# RK3566_FLASH_SD.net
KiCad netlist of a schematic drawn in Altium Designer
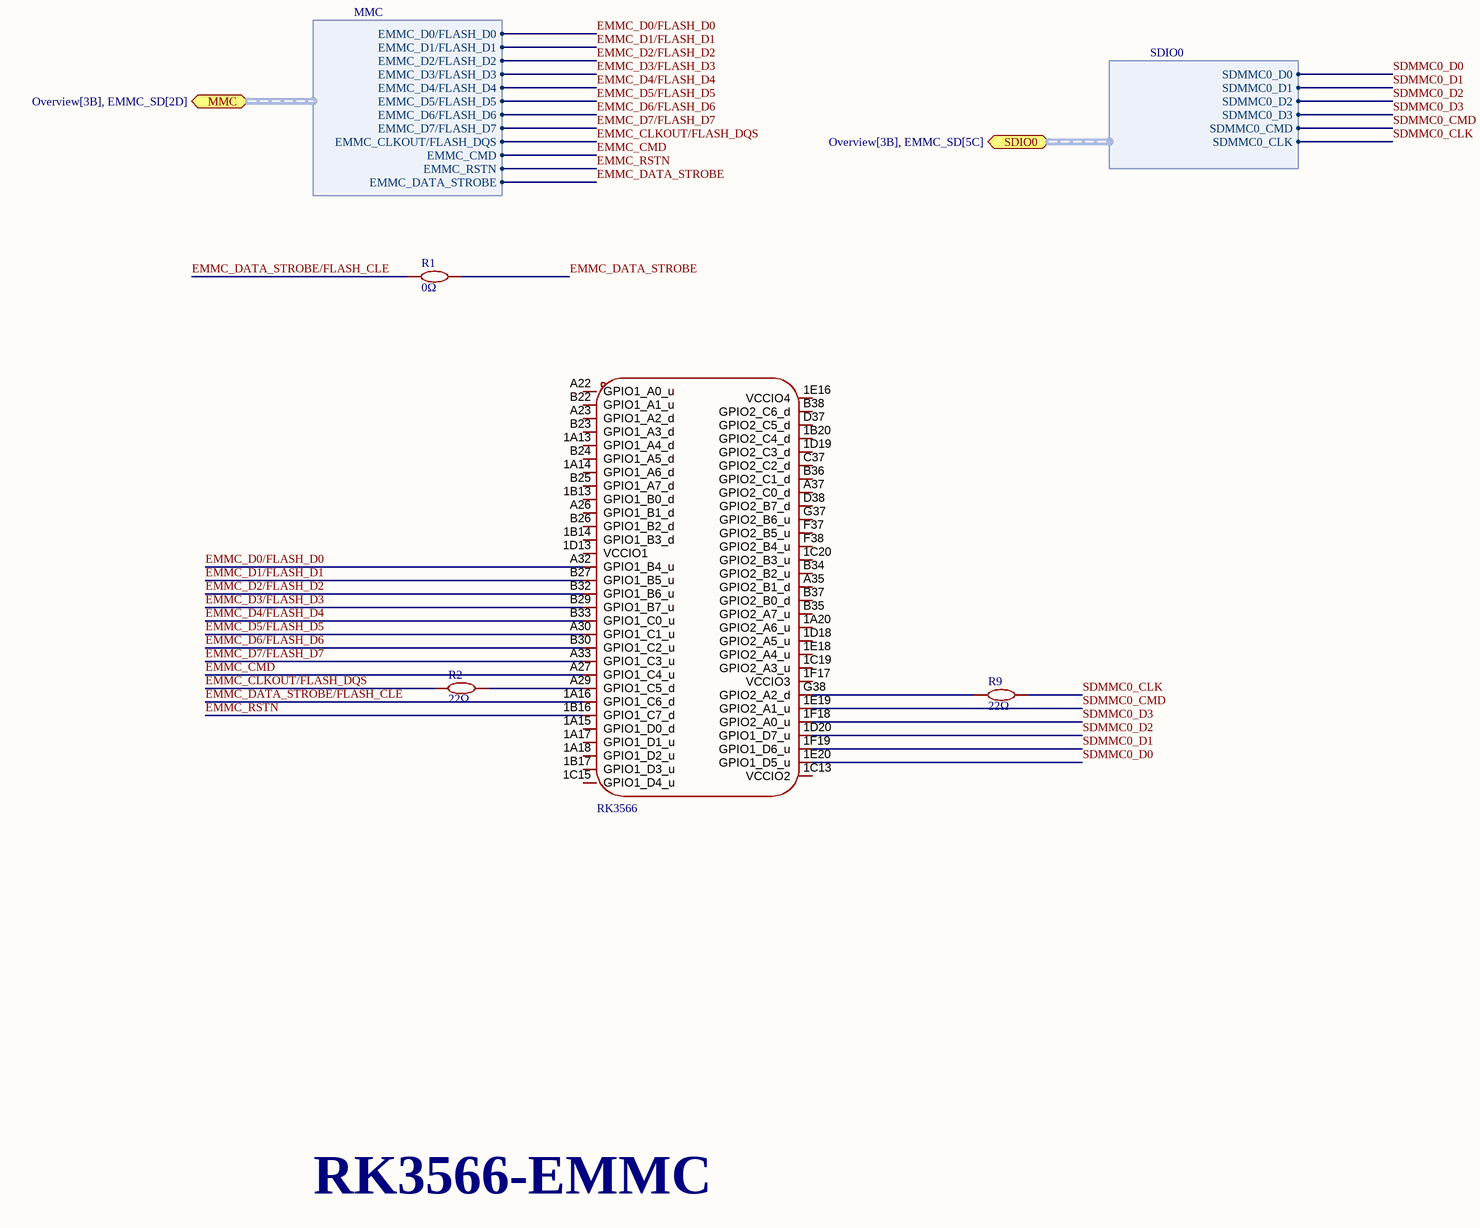
[diagram p0: RK3566_FLASH_SD.SchDoc]

(export (version "E")
  (design (tool "Eeschema 10.0.6"))
  (components
    (comp (ref "R1")
      (value "0Ω")
      (footprint "R0402")
      (description "0Ω 62.5mW 50V Thick Film Resistor ±1% 0402 Chip Resistor - Surface Mount ROHS")
      (libsource (lib "RLC") (part "0Ω"))
    )
    (comp (ref "R2")
      (value "22Ω")
      (footprint "R0402")
      (description "62.5mW 33Ω 50V ±100ppm/℃ Thick Film Resistor ±1% 0402 Chip Resistor - Surface Mount ROHS")
      (libsource (lib "RLC") (part "22Ω"))
    )
    (comp (ref "R9")
      (value "22Ω")
      (footprint "R0402")
      (description "62.5mW 33Ω 50V ±100ppm/℃ Thick Film Resistor ±1% 0402 Chip Resistor - Surface Mount ROHS")
      (libsource (lib "RLC") (part "22Ω"))
    )
    (comp (ref "U1")
      (value "RK3566")
      (footprint "BGA-565_L15.5-W14.4-P0.40_RK3566_1")
      (description "BGA-565(15.5x14.4)")
      (libsource (lib "IC") (part "RK3566"))
    )
  )
  (nets
    (net (code "3") (name "/EMMC_CLKOUT{slash}FLASH_DQS") (class "Default")
      (node (ref "R2") (pin "1") (pinfunction "1_1") (pintype "passive"))
    )
    (net (code "4") (name "/EMMC_CMD") (class "Default")
      (node (ref "U1") (pin "A27") (pinfunction "GPIO1_C4_u_A27") (pintype "passive"))
    )
    (net (code "5") (name "/EMMC_D0{slash}FLASH_D0") (class "Default")
      (node (ref "U1") (pin "A32") (pinfunction "GPIO1_B4_u_A32") (pintype "passive"))
    )
    (net (code "6") (name "/EMMC_D1{slash}FLASH_D1") (class "Default")
      (node (ref "U1") (pin "B27") (pinfunction "GPIO1_B5_u_B27") (pintype "passive"))
    )
    (net (code "7") (name "/EMMC_D2{slash}FLASH_D2") (class "Default")
      (node (ref "U1") (pin "B32") (pinfunction "GPIO1_B6_u_B32") (pintype "passive"))
    )
    (net (code "8") (name "/EMMC_D3{slash}FLASH_D3") (class "Default")
      (node (ref "U1") (pin "B29") (pinfunction "GPIO1_B7_u_B29") (pintype "passive"))
    )
    (net (code "9") (name "/EMMC_D4{slash}FLASH_D4") (class "Default")
      (node (ref "U1") (pin "B33") (pinfunction "GPIO1_C0_u_B33") (pintype "passive"))
    )
    (net (code "10") (name "/EMMC_D5{slash}FLASH_D5") (class "Default")
      (node (ref "U1") (pin "A30") (pinfunction "GPIO1_C1_u_A30") (pintype "passive"))
    )
    (net (code "11") (name "/EMMC_D6{slash}FLASH_D6") (class "Default")
      (node (ref "U1") (pin "B30") (pinfunction "GPIO1_C2_u_B30") (pintype "passive"))
    )
    (net (code "12") (name "/EMMC_D7{slash}FLASH_D7") (class "Default")
      (node (ref "U1") (pin "A33") (pinfunction "GPIO1_C3_u_A33") (pintype "passive"))
    )
    (net (code "13") (name "/EMMC_DATA_STROBE") (class "Default")
      (node (ref "R1") (pin "2") (pinfunction "2_2") (pintype "passive"))
    )
    (net (code "14") (name "/EMMC_DATA_STROBE{slash}FLASH_CLE") (class "Default")
      (node (ref "R1") (pin "1") (pinfunction "1_1") (pintype "passive"))
      (node (ref "U1") (pin "1A16") (pinfunction "GPIO1_C6_d_1A16") (pintype "passive"))
    )
    (net (code "15") (name "/EMMC_RSTN") (class "Default")
      (node (ref "U1") (pin "1B16") (pinfunction "GPIO1_C7_d_1B16") (pintype "passive"))
    )
    (net (code "16") (name "/SDMMC0_CLK") (class "Default")
      (node (ref "R9") (pin "2") (pinfunction "2_2") (pintype "passive"))
    )
    (net (code "17") (name "/SDMMC0_CMD") (class "Default")
      (node (ref "U1") (pin "1E19") (pinfunction "GPIO2_A1_u_1E19") (pintype "passive"))
    )
    (net (code "18") (name "/SDMMC0_D0") (class "Default")
      (node (ref "U1") (pin "1E20") (pinfunction "GPIO1_D5_u_1E20") (pintype "passive"))
    )
    (net (code "19") (name "/SDMMC0_D1") (class "Default")
      (node (ref "U1") (pin "1F19") (pinfunction "GPIO1_D6_u_1F19") (pintype "passive"))
    )
    (net (code "20") (name "/SDMMC0_D2") (class "Default")
      (node (ref "U1") (pin "1D20") (pinfunction "GPIO1_D7_u_1D20") (pintype "passive"))
    )
    (net (code "21") (name "/SDMMC0_D3") (class "Default")
      (node (ref "U1") (pin "1F18") (pinfunction "GPIO2_A0_u_1F18") (pintype "passive"))
    )
    (net (code "24") (name "Net-(U1E-GPIO1_C5_d)") (class "Default")
      (node (ref "R2") (pin "2") (pinfunction "2_2") (pintype "passive"))
      (node (ref "U1") (pin "A29") (pinfunction "GPIO1_C5_d_A29") (pintype "passive"))
    )
    (net (code "25") (name "Net-(U1E-GPIO2_A2_d)") (class "Default")
      (node (ref "R9") (pin "1") (pinfunction "1_1") (pintype "passive"))
      (node (ref "U1") (pin "G38") (pinfunction "GPIO2_A2_d_G38") (pintype "passive"))
    )
    (net (code "26") (name "unconnected-(U1E-GPIO1_A0_u-PadA22)") (class "Default")
      (node (ref "U1") (pin "A22") (pinfunction "GPIO1_A0_u_A22") (pintype "passive"))
    )
    (net (code "27") (name "unconnected-(U1E-GPIO1_A1_u-PadB22)") (class "Default")
      (node (ref "U1") (pin "B22") (pinfunction "GPIO1_A1_u_B22") (pintype "passive"))
    )
    (net (code "28") (name "unconnected-(U1E-GPIO1_A2_d-PadA23)") (class "Default")
      (node (ref "U1") (pin "A23") (pinfunction "GPIO1_A2_d_A23") (pintype "passive"))
    )
    (net (code "29") (name "unconnected-(U1E-GPIO1_A3_d-PadB23)") (class "Default")
      (node (ref "U1") (pin "B23") (pinfunction "GPIO1_A3_d_B23") (pintype "passive"))
    )
    (net (code "30") (name "unconnected-(U1E-GPIO1_A4_d-Pad1A13)") (class "Default")
      (node (ref "U1") (pin "1A13") (pinfunction "GPIO1_A4_d_1A13") (pintype "passive"))
    )
    (net (code "31") (name "unconnected-(U1E-GPIO1_A5_d-PadB24)") (class "Default")
      (node (ref "U1") (pin "B24") (pinfunction "GPIO1_A5_d_B24") (pintype "passive"))
    )
    (net (code "32") (name "unconnected-(U1E-GPIO1_A6_d-Pad1A14)") (class "Default")
      (node (ref "U1") (pin "1A14") (pinfunction "GPIO1_A6_d_1A14") (pintype "passive"))
    )
    (net (code "33") (name "unconnected-(U1E-GPIO1_A7_d-PadB25)") (class "Default")
      (node (ref "U1") (pin "B25") (pinfunction "GPIO1_A7_d_B25") (pintype "passive"))
    )
    (net (code "34") (name "unconnected-(U1E-GPIO1_B0_d-Pad1B13)") (class "Default")
      (node (ref "U1") (pin "1B13") (pinfunction "GPIO1_B0_d_1B13") (pintype "passive"))
    )
    (net (code "35") (name "unconnected-(U1E-GPIO1_B1_d-PadA26)") (class "Default")
      (node (ref "U1") (pin "A26") (pinfunction "GPIO1_B1_d_A26") (pintype "passive"))
    )
    (net (code "36") (name "unconnected-(U1E-GPIO1_B2_d-PadB26)") (class "Default")
      (node (ref "U1") (pin "B26") (pinfunction "GPIO1_B2_d_B26") (pintype "passive"))
    )
    (net (code "37") (name "unconnected-(U1E-GPIO1_B3_d-Pad1B14)") (class "Default")
      (node (ref "U1") (pin "1B14") (pinfunction "GPIO1_B3_d_1B14") (pintype "passive"))
    )
    (net (code "38") (name "unconnected-(U1E-GPIO1_D0_d-Pad1A15)") (class "Default")
      (node (ref "U1") (pin "1A15") (pinfunction "GPIO1_D0_d_1A15") (pintype "passive"))
    )
    (net (code "39") (name "unconnected-(U1E-GPIO1_D1_u-Pad1A17)") (class "Default")
      (node (ref "U1") (pin "1A17") (pinfunction "GPIO1_D1_u_1A17") (pintype "passive"))
    )
    (net (code "40") (name "unconnected-(U1E-GPIO1_D2_u-Pad1A18)") (class "Default")
      (node (ref "U1") (pin "1A18") (pinfunction "GPIO1_D2_u_1A18") (pintype "passive"))
    )
    (net (code "41") (name "unconnected-(U1E-GPIO1_D3_u-Pad1B17)") (class "Default")
      (node (ref "U1") (pin "1B17") (pinfunction "GPIO1_D3_u_1B17") (pintype "passive"))
    )
    (net (code "42") (name "unconnected-(U1E-GPIO1_D4_u-Pad1C15)") (class "Default")
      (node (ref "U1") (pin "1C15") (pinfunction "GPIO1_D4_u_1C15") (pintype "passive"))
    )
    (net (code "43") (name "unconnected-(U1E-GPIO2_A3_u-Pad1C19)") (class "Default")
      (node (ref "U1") (pin "1C19") (pinfunction "GPIO2_A3_u_1C19") (pintype "passive"))
    )
    (net (code "44") (name "unconnected-(U1E-GPIO2_A4_u-Pad1E18)") (class "Default")
      (node (ref "U1") (pin "1E18") (pinfunction "GPIO2_A4_u_1E18") (pintype "passive"))
    )
    (net (code "45") (name "unconnected-(U1E-GPIO2_A5_u-Pad1D18)") (class "Default")
      (node (ref "U1") (pin "1D18") (pinfunction "GPIO2_A5_u_1D18") (pintype "passive"))
    )
    (net (code "46") (name "unconnected-(U1E-GPIO2_A6_u-Pad1A20)") (class "Default")
      (node (ref "U1") (pin "1A20") (pinfunction "GPIO2_A6_u_1A20") (pintype "passive"))
    )
    (net (code "47") (name "unconnected-(U1E-GPIO2_A7_u-PadB35)") (class "Default")
      (node (ref "U1") (pin "B35") (pinfunction "GPIO2_A7_u_B35") (pintype "passive"))
    )
    (net (code "48") (name "unconnected-(U1E-GPIO2_B0_d-PadB37)") (class "Default")
      (node (ref "U1") (pin "B37") (pinfunction "GPIO2_B0_d_B37") (pintype "passive"))
    )
    (net (code "49") (name "unconnected-(U1E-GPIO2_B1_d-PadA35)") (class "Default")
      (node (ref "U1") (pin "A35") (pinfunction "GPIO2_B1_d_A35") (pintype "passive"))
    )
    (net (code "50") (name "unconnected-(U1E-GPIO2_B2_u-PadB34)") (class "Default")
      (node (ref "U1") (pin "B34") (pinfunction "GPIO2_B2_u_B34") (pintype "passive"))
    )
    (net (code "51") (name "unconnected-(U1E-GPIO2_B3_u-Pad1C20)") (class "Default")
      (node (ref "U1") (pin "1C20") (pinfunction "GPIO2_B3_u_1C20") (pintype "passive"))
    )
    (net (code "52") (name "unconnected-(U1E-GPIO2_B4_u-PadF38)") (class "Default")
      (node (ref "U1") (pin "F38") (pinfunction "GPIO2_B4_u_F38") (pintype "passive"))
    )
    (net (code "53") (name "unconnected-(U1E-GPIO2_B5_u-PadF37)") (class "Default")
      (node (ref "U1") (pin "F37") (pinfunction "GPIO2_B5_u_F37") (pintype "passive"))
    )
    (net (code "54") (name "unconnected-(U1E-GPIO2_B6_u-PadG37)") (class "Default")
      (node (ref "U1") (pin "G37") (pinfunction "GPIO2_B6_u_G37") (pintype "passive"))
    )
    (net (code "55") (name "unconnected-(U1E-GPIO2_B7_d-PadD38)") (class "Default")
      (node (ref "U1") (pin "D38") (pinfunction "GPIO2_B7_d_D38") (pintype "passive"))
    )
    (net (code "56") (name "unconnected-(U1E-GPIO2_C0_d-PadA37)") (class "Default")
      (node (ref "U1") (pin "A37") (pinfunction "GPIO2_C0_d_A37") (pintype "passive"))
    )
    (net (code "57") (name "unconnected-(U1E-GPIO2_C1_d-PadB36)") (class "Default")
      (node (ref "U1") (pin "B36") (pinfunction "GPIO2_C1_d_B36") (pintype "passive"))
    )
    (net (code "58") (name "unconnected-(U1E-GPIO2_C2_d-PadC37)") (class "Default")
      (node (ref "U1") (pin "C37") (pinfunction "GPIO2_C2_d_C37") (pintype "passive"))
    )
    (net (code "59") (name "unconnected-(U1E-GPIO2_C3_d-Pad1D19)") (class "Default")
      (node (ref "U1") (pin "1D19") (pinfunction "GPIO2_C3_d_1D19") (pintype "passive"))
    )
    (net (code "60") (name "unconnected-(U1E-GPIO2_C4_d-Pad1B20)") (class "Default")
      (node (ref "U1") (pin "1B20") (pinfunction "GPIO2_C4_d_1B20") (pintype "passive"))
    )
    (net (code "61") (name "unconnected-(U1E-GPIO2_C5_d-PadD37)") (class "Default")
      (node (ref "U1") (pin "D37") (pinfunction "GPIO2_C5_d_D37") (pintype "passive"))
    )
    (net (code "62") (name "unconnected-(U1E-GPIO2_C6_d-PadB38)") (class "Default")
      (node (ref "U1") (pin "B38") (pinfunction "GPIO2_C6_d_B38") (pintype "passive"))
    )
    (net (code "63") (name "unconnected-(U1E-VCCIO1-Pad1D13)") (class "Default")
      (node (ref "U1") (pin "1D13") (pinfunction "VCCIO1_1D13") (pintype "passive"))
    )
    (net (code "64") (name "unconnected-(U1E-VCCIO2-Pad1C13)") (class "Default")
      (node (ref "U1") (pin "1C13") (pinfunction "VCCIO2_1C13") (pintype "passive"))
    )
    (net (code "65") (name "unconnected-(U1E-VCCIO3-Pad1F17)") (class "Default")
      (node (ref "U1") (pin "1F17") (pinfunction "VCCIO3_1F17") (pintype "passive"))
    )
    (net (code "66") (name "unconnected-(U1E-VCCIO4-Pad1E16)") (class "Default")
      (node (ref "U1") (pin "1E16") (pinfunction "VCCIO4_1E16") (pintype "passive"))
    )
  )
)
